# AutoDoor_App.net
KiCad netlist of a schematic drawn in Altium Designer
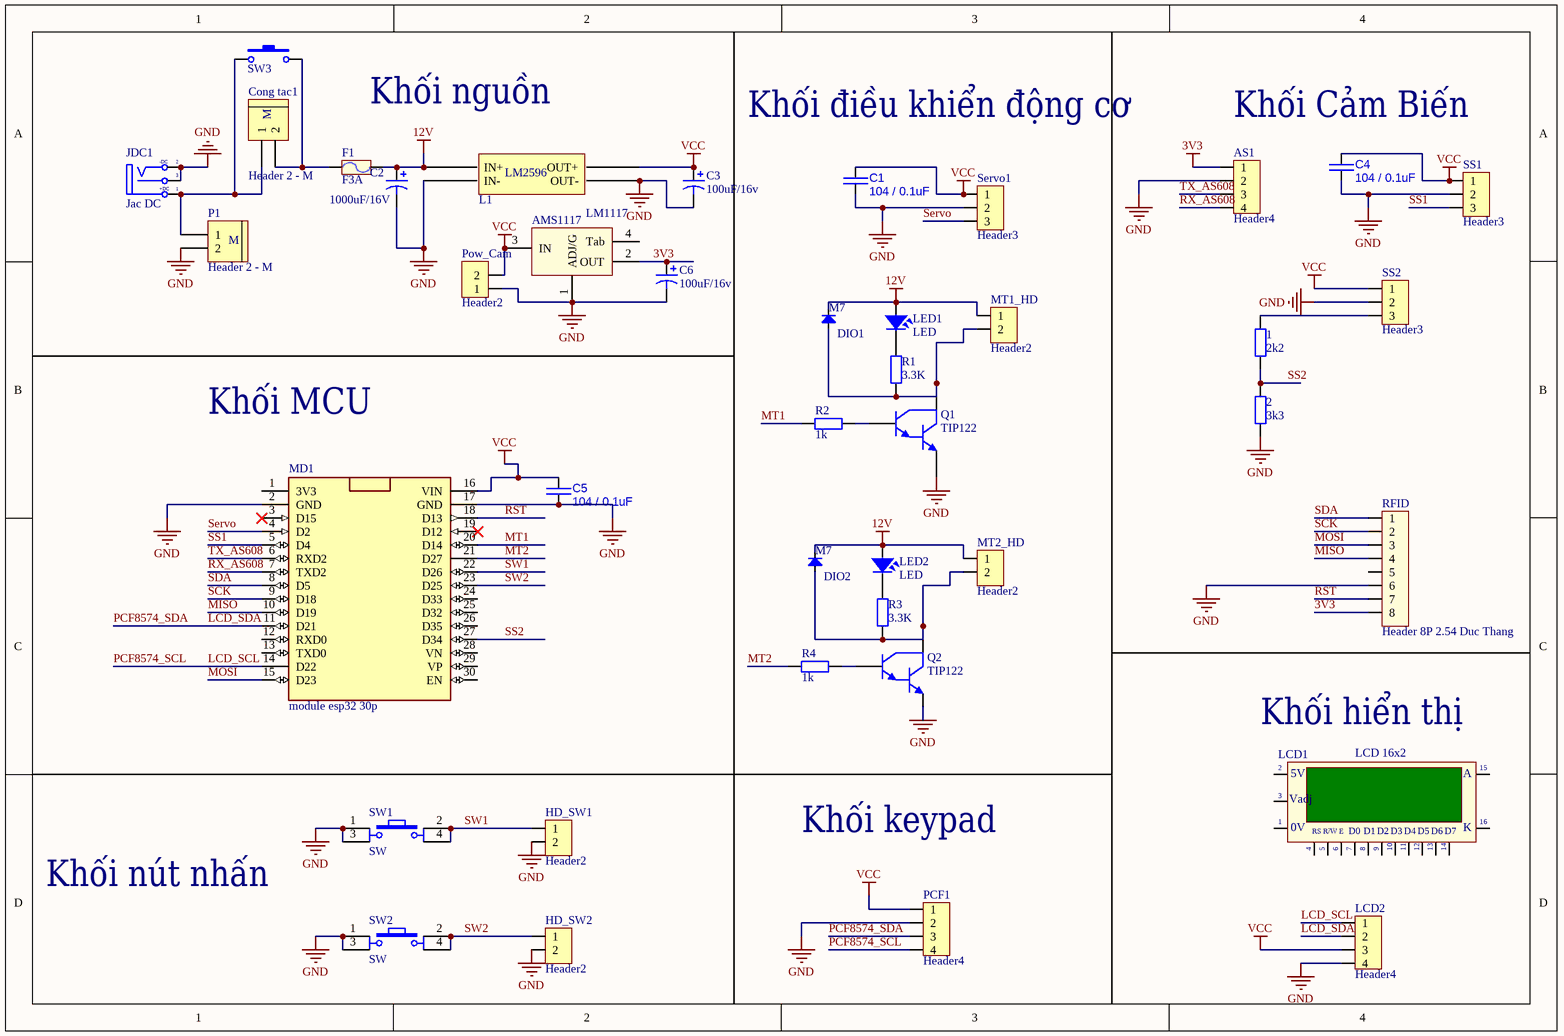
[diagram p0: AutoDoor_App.SchDoc]

(export (version "E")
  (design (tool "Eeschema 10.0.6"))
  (components
    (comp (ref "1")
      (value "2k2")
      (footprint "DIEN TRO 0805")
      (description "Resistor SMD 0805")
      (fields (field (name "PUBLISHER") "Altium Limited"))
      (libsource (lib "My Library (1)") (part "R0805"))
    )
    (comp (ref "2")
      (value "3k3")
      (footprint "DIEN TRO 0805")
      (description "Resistor SMD 0805")
      (fields (field (name "PUBLISHER") "Altium Limited"))
      (libsource (lib "My Library (1)") (part "R0805"))
    )
    (comp (ref "AMS1117")
      (value "LM1117")
      (footprint "SOT223-4N")
      (description "3v3")
      (libsource (lib "My Library") (part "LM1117"))
    )
    (comp (ref "AS1")
      (value "Header4")
      (footprint "Header4")
      (description "Header IDC, 4 x 1 Pin Vertical 2.54mm Pitch (Non-Boxed, Male)")
      (fields
        (field (name "MANUFACTURER") "Würth Elektronik eiSos GmbH")
        (field (name "PARTNO") "613002143121")
        (field (name "CREATED BY") "Karrer Zheng")
      )
      (libsource (lib "My Library") (part "Header4"))
    )
    (comp (ref "C1")
      (value "104 / 0.1uF")
      (footprint "CAP_0805")
      (description "Capacitor SMD Cer 1.8nF 10% 50V X7R 0805")
      (fields (field (name "TOLERANCE") "±10%") (field (name "Comment") "approved sub OK"))
      (libsource (lib "My library altium") (part "CAP C_0805"))
    )
    (comp (ref "C2")
      (value "1000uF/16V")
      (footprint "C10mm")
      (description "Polarized Capacitor (Axial)")
      (fields (field (name "PUBLISHER") "Altium Limited"))
      (libsource (lib "My Library") (part "Cap Pol 12mm"))
    )
    (comp (ref "C3")
      (value "100uF/16v")
      (footprint "C5mm")
      (description "Polarized Capacitor (Axial)")
      (fields (field (name "PUBLISHER") "Altium Limited"))
      (libsource (lib "My Library") (part "Cap Pol 5mm"))
    )
    (comp (ref "C4")
      (value "104 / 0.1uF")
      (footprint "CAP_0805")
      (description "Capacitor SMD Cer 1.8nF 10% 50V X7R 0805")
      (fields (field (name "TOLERANCE") "±10%") (field (name "Comment") "approved sub OK"))
      (libsource (lib "My library altium") (part "CAP C_0805"))
    )
    (comp (ref "C5")
      (value "104 / 0.1uF")
      (footprint "CAP_0805")
      (description "Capacitor SMD Cer 1.8nF 10% 50V X7R 0805")
      (fields (field (name "TOLERANCE") "±10%") (field (name "Comment") "approved sub OK"))
      (libsource (lib "My library altium") (part "CAP C_0805"))
    )
    (comp (ref "C6")
      (value "100uF/16v")
      (footprint "C5mm")
      (description "Polarized Capacitor (Axial)")
      (fields (field (name "PUBLISHER") "Altium Limited"))
      (libsource (lib "My Library") (part "Cap Pol 5mm"))
    )
    (comp (ref "Cong tac1")
      (value "Header 2 - M")
      (footprint "Medium - Header 2")
      (description "Header, 2-Pin, Medium")
      (fields (field (name "PUBLISHER") "Altium Limited"))
      (libsource (lib "My Library") (part "Header 2 - M"))
    )
    (comp (ref "DIO1")
      (value "M7")
      (footprint "DIO-SMD-106")
      (description "Default Diode")
      (fields (field (name "PUBLISHER") "Altium Limited"))
      (libsource (lib "My Library (1)") (part "Diode SMD"))
    )
    (comp (ref "DIO2")
      (value "M7")
      (footprint "DIO-SMD-106")
      (description "Default Diode")
      (fields (field (name "PUBLISHER") "Altium Limited"))
      (libsource (lib "My Library (1)") (part "Diode SMD"))
    )
    (comp (ref "F1")
      (value "F3A")
      (footprint "Fuse")
      (description "Fuse")
      (fields (field (name "DESIGNED BY") "VanDungEvn"))
      (libsource (lib "My Library") (part "Fuse"))
    )
    (comp (ref "HD_SW1")
      (value "Header2")
      (footprint "Header2")
      (description "Header IDC, 2 x 1 Pin Vertical 2.54mm Pitch (Non-Boxed, Male)")
      (fields
        (field (name "MANUFACTURER") "Würth Elektronik eiSos GmbH")
        (field (name "PARTNO") "613002143121")
        (field (name "CREATED BY") "Karrer Zheng")
      )
      (libsource (lib "My Library") (part "Header2"))
    )
    (comp (ref "HD_SW2")
      (value "Header2")
      (footprint "Header2")
      (description "Header IDC, 2 x 1 Pin Vertical 2.54mm Pitch (Non-Boxed, Male)")
      (fields
        (field (name "MANUFACTURER") "Würth Elektronik eiSos GmbH")
        (field (name "PARTNO") "613002143121")
        (field (name "CREATED BY") "Karrer Zheng")
      )
      (libsource (lib "My Library") (part "Header2"))
    )
    (comp (ref "JDC1")
      (value "Jac DC")
      (footprint "DC-IN")
      (description "Jac DC input")
      (libsource (lib "My Library") (part "DCIN"))
    )
    (comp (ref "L1")
      (value "BUCK_LM2596")
      (footprint "BUCK_LM2596")
      (libsource (lib "BUCK_LM2596_Sch") (part "BUCK_LM2596"))
    )
    (comp (ref "LCD1")
      (value "LCD 16x2")
      (footprint "LCD16X2N")
      (libsource (lib "My library altium") (part "LCD"))
    )
    (comp (ref "LCD2")
      (value "Header4")
      (footprint "XH2.54M-4")
      (description "Header IDC, 4 x 1 Pin Vertical 2.54mm Pitch (Non-Boxed, Male)")
      (fields
        (field (name "MANUFACTURER") "Würth Elektronik eiSos GmbH")
        (field (name "PARTNO") "613002143121")
        (field (name "CREATED BY") "Karrer Zheng")
      )
      (libsource (lib "My Library") (part "Header4"))
    )
    (comp (ref "LED1")
      (value "LED")
      (footprint "LED-5 GRe")
      (description "LED Single colour Green and Red")
      (libsource (lib "My Library") (part "LED"))
    )
    (comp (ref "LED2")
      (value "LED")
      (footprint "LED-5 GRe")
      (description "LED Single colour Green and Red")
      (libsource (lib "My Library") (part "LED"))
    )
    (comp (ref "MD1")
      (value "module esp32 30p")
      (footprint "module esp32 30 pin")
      (libsource (lib "Chuong Engineer") (part "module esp32 30p"))
    )
    (comp (ref "MT1_HD")
      (value "Header2")
      (footprint "Header2")
      (description "Header IDC, 2 x 1 Pin Vertical 2.54mm Pitch (Non-Boxed, Male)")
      (fields
        (field (name "MANUFACTURER") "Würth Elektronik eiSos GmbH")
        (field (name "PARTNO") "613002143121")
        (field (name "CREATED BY") "Karrer Zheng")
      )
      (libsource (lib "My Library") (part "Header2"))
    )
    (comp (ref "MT2_HD")
      (value "Header2")
      (footprint "Header2")
      (description "Header IDC, 2 x 1 Pin Vertical 2.54mm Pitch (Non-Boxed, Male)")
      (fields
        (field (name "MANUFACTURER") "Würth Elektronik eiSos GmbH")
        (field (name "PARTNO") "613002143121")
        (field (name "CREATED BY") "Karrer Zheng")
      )
      (libsource (lib "My Library") (part "Header2"))
    )
    (comp (ref "P1")
      (value "Header 2 - M")
      (footprint "Medium - Header 2")
      (description "Header, 2-Pin, Medium")
      (fields (field (name "PUBLISHER") "Altium Limited"))
      (libsource (lib "") (part "Header 2 - M_1"))
    )
    (comp (ref "PCF1")
      (value "Header4")
      (footprint "XH2.54M-4")
      (description "Header IDC, 4 x 1 Pin Vertical 2.54mm Pitch (Non-Boxed, Male)")
      (fields
        (field (name "MANUFACTURER") "Würth Elektronik eiSos GmbH")
        (field (name "PARTNO") "613002143121")
        (field (name "CREATED BY") "Karrer Zheng")
      )
      (libsource (lib "My Library") (part "Header4"))
    )
    (comp (ref "Pow_Cam")
      (value "Header2")
      (footprint "Header2")
      (description "Header IDC, 2 x 1 Pin Vertical 2.54mm Pitch (Non-Boxed, Male)")
      (fields
        (field (name "MANUFACTURER") "Würth Elektronik eiSos GmbH")
        (field (name "PARTNO") "613002143121")
        (field (name "CREATED BY") "Karrer Zheng")
      )
      (libsource (lib "") (part "Header2_1"))
    )
    (comp (ref "Q1")
      (value "TIP122")
      (footprint "QTO-220")
      (description "Darlington Silicon Power NPN Transistor, 8 Amp, 100 Volts and 65 Watts")
      (libsource (lib "My Library (1)") (part "TIP122"))
    )
    (comp (ref "Q2")
      (value "TIP122")
      (footprint "QTO-220")
      (description "Darlington Silicon Power NPN Transistor, 8 Amp, 100 Volts and 65 Watts")
      (libsource (lib "My Library (1)") (part "TIP122"))
    )
    (comp (ref "R1")
      (value "3.3K")
      (footprint "DIEN TRO 0805")
      (description "Resistor SMD 0805")
      (fields (field (name "PUBLISHER") "Altium Limited"))
      (libsource (lib "My Library (1)") (part "R0805"))
    )
    (comp (ref "R2")
      (value "1k")
      (footprint "DIEN TRO 0805")
      (description "Resistor SMD 0805")
      (fields (field (name "PUBLISHER") "Altium Limited"))
      (libsource (lib "") (part "R0805_1"))
    )
    (comp (ref "R3")
      (value "3.3K")
      (footprint "DIEN TRO 0805")
      (description "Resistor SMD 0805")
      (fields (field (name "PUBLISHER") "Altium Limited"))
      (libsource (lib "My Library (1)") (part "R0805"))
    )
    (comp (ref "R4")
      (value "1k")
      (footprint "DIEN TRO 0805")
      (description "Resistor SMD 0805")
      (fields (field (name "PUBLISHER") "Altium Limited"))
      (libsource (lib "") (part "R0805_1"))
    )
    (comp (ref "RFID")
      (value "Header 8P 2.54 Duc Thang")
      (footprint "XH2.54M-8")
      (description "Cắm")
      (libsource (lib "Header") (part "Header 8P 2.54 Duc Thang"))
    )
    (comp (ref "Servo1")
      (value "Header3")
      (footprint "Header3")
      (description "Header IDC, 3 x 1 Pin Vertical 2.54mm Pitch (Non-Boxed, Male)")
      (fields
        (field (name "MANUFACTURER") "Würth Elektronik eiSos GmbH")
        (field (name "PARTNO") "613002143121")
        (field (name "CREATED BY") "Karrer Zheng")
      )
      (libsource (lib "My Library") (part "Header3"))
    )
    (comp (ref "SS1")
      (value "Header3")
      (footprint "Header3")
      (description "Header IDC, 3 x 1 Pin Vertical 2.54mm Pitch (Non-Boxed, Male)")
      (fields
        (field (name "MANUFACTURER") "Würth Elektronik eiSos GmbH")
        (field (name "PARTNO") "613002143121")
        (field (name "CREATED BY") "Karrer Zheng")
      )
      (libsource (lib "My Library") (part "Header3"))
    )
    (comp (ref "SS2")
      (value "Header3")
      (footprint "Header3")
      (description "Header IDC, 3 x 1 Pin Vertical 2.54mm Pitch (Non-Boxed, Male)")
      (fields
        (field (name "MANUFACTURER") "Würth Elektronik eiSos GmbH")
        (field (name "PARTNO") "613002143121")
        (field (name "CREATED BY") "Karrer Zheng")
      )
      (libsource (lib "My Library") (part "Header3"))
    )
    (comp (ref "SW1")
      (value "SW")
      (footprint "SW4")
      (description "Switch button 4 pin")
      (libsource (lib "My Library (1)") (part "SW4"))
    )
    (comp (ref "SW2")
      (value "SW")
      (footprint "SW4")
      (description "Switch button 4 pin")
      (libsource (lib "My Library (1)") (part "SW4"))
    )
    (comp (ref "SW3")
      (value "KCD01-11_SWITCH")
      (footprint "KCD01-11")
      (description "Nut Nhan 2 Chan SMD 3x6x2.5")
      (libsource (lib "KS Chuong") (part "KCD01-11_SWITCH"))
    )
  )
  (nets
    (net (code "1") (name "/LCD_SCL") (class "Default")
      (node (ref "LCD2") (pin "1") (pinfunction "1_1") (pintype "passive"))
      (node (ref "MD1") (pin "14") (pinfunction "D22_14") (pintype "power_in"))
      (node (ref "PCF1") (pin "4") (pinfunction "4_4") (pintype "passive"))
    )
    (net (code "2") (name "/LCD_SDA") (class "Default")
      (node (ref "LCD2") (pin "2") (pinfunction "2_2") (pintype "passive"))
      (node (ref "MD1") (pin "11") (pinfunction "D21_11") (pintype "bidirectional"))
      (node (ref "PCF1") (pin "3") (pinfunction "3_3") (pintype "passive"))
    )
    (net (code "3") (name "/MISO") (class "Default")
      (node (ref "MD1") (pin "10") (pinfunction "D19_10") (pintype "bidirectional"))
      (node (ref "RFID") (pin "4") (pinfunction "4_4") (pintype "passive"))
    )
    (net (code "4") (name "/MOSI") (class "Default")
      (node (ref "MD1") (pin "15") (pinfunction "D23_15") (pintype "bidirectional"))
      (node (ref "RFID") (pin "3") (pinfunction "3_3") (pintype "passive"))
    )
    (net (code "5") (name "/MT1") (class "Default")
      (node (ref "MD1") (pin "20") (pinfunction "D14_20") (pintype "bidirectional"))
      (node (ref "R2") (pin "2") (pinfunction "2_2") (pintype "passive"))
    )
    (net (code "6") (name "/MT2") (class "Default")
      (node (ref "MD1") (pin "21") (pinfunction "D27_21") (pintype "power_in"))
      (node (ref "R4") (pin "2") (pinfunction "2_2") (pintype "passive"))
    )
    (net (code "7") (name "/RST") (class "Default")
      (node (ref "MD1") (pin "18") (pinfunction "D13_18") (pintype "output"))
      (node (ref "RFID") (pin "7") (pinfunction "7_7") (pintype "passive"))
    )
    (net (code "8") (name "/RX_AS608") (class "Default")
      (node (ref "AS1") (pin "4") (pinfunction "4_4") (pintype "passive"))
      (node (ref "MD1") (pin "7") (pinfunction "TXD2_7") (pintype "bidirectional"))
    )
    (net (code "9") (name "/SCK") (class "Default")
      (node (ref "MD1") (pin "9") (pinfunction "D18_9") (pintype "bidirectional"))
      (node (ref "RFID") (pin "2") (pinfunction "2_2") (pintype "passive"))
    )
    (net (code "10") (name "/SDA") (class "Default")
      (node (ref "MD1") (pin "8") (pinfunction "D5_8") (pintype "bidirectional"))
      (node (ref "RFID") (pin "1") (pinfunction "1_1") (pintype "passive"))
    )
    (net (code "11") (name "/SS1") (class "Default")
      (node (ref "MD1") (pin "5") (pinfunction "D4_5") (pintype "bidirectional"))
      (node (ref "SS1") (pin "3") (pinfunction "3_3") (pintype "passive"))
    )
    (net (code "12") (name "/SS2") (class "Default")
      (node (ref "1") (pin "2") (pinfunction "2_2") (pintype "passive"))
      (node (ref "2") (pin "1") (pinfunction "1_1") (pintype "passive"))
      (node (ref "MD1") (pin "27") (pinfunction "D34_27") (pintype "bidirectional"))
    )
    (net (code "13") (name "/SW1") (class "Default")
      (node (ref "HD_SW1") (pin "1") (pinfunction "1_1") (pintype "passive"))
      (node (ref "MD1") (pin "22") (pinfunction "D26_22") (pintype "bidirectional"))
      (node (ref "SW1") (pin "2") (pintype "passive"))
      (node (ref "SW1") (pin "4") (pintype "passive"))
    )
    (net (code "14") (name "/SW2") (class "Default")
      (node (ref "HD_SW2") (pin "1") (pinfunction "1_1") (pintype "passive"))
      (node (ref "MD1") (pin "23") (pinfunction "D25_23") (pintype "bidirectional"))
      (node (ref "SW2") (pin "2") (pintype "passive"))
      (node (ref "SW2") (pin "4") (pintype "passive"))
    )
    (net (code "15") (name "/Servo") (class "Default")
      (node (ref "MD1") (pin "4") (pinfunction "D2_4") (pintype "input"))
      (node (ref "Servo1") (pin "3") (pinfunction "3_3") (pintype "passive"))
    )
    (net (code "16") (name "/TX_AS608") (class "Default")
      (node (ref "AS1") (pin "3") (pinfunction "3_3") (pintype "passive"))
      (node (ref "MD1") (pin "6") (pinfunction "RXD2_6") (pintype "bidirectional"))
    )
    (net (code "17") (name "3V3") (class "Default")
      (node (ref "AMS1117") (pin "2") (pinfunction "OUT_2") (pintype "passive"))
      (node (ref "AS1") (pin "1") (pinfunction "1_1") (pintype "passive"))
      (node (ref "C6") (pin "1") (pinfunction "1_1") (pintype "passive"))
      (node (ref "RFID") (pin "8") (pinfunction "8_8") (pintype "passive"))
    )
    (net (code "18") (name "12V") (class "Default")
      (node (ref "C2") (pin "1") (pinfunction "1_1") (pintype "passive"))
      (node (ref "DIO1") (pin "2") (pinfunction "K_2") (pintype "passive"))
      (node (ref "DIO2") (pin "2") (pinfunction "K_2") (pintype "passive"))
      (node (ref "F1") (pin "2") (pinfunction "2_2") (pintype "passive"))
      (node (ref "L1") (pin "1") (pinfunction "IN+_1") (pintype "passive"))
      (node (ref "LED1") (pin "1") (pinfunction "1_1") (pintype "passive"))
      (node (ref "LED2") (pin "1") (pinfunction "1_1") (pintype "passive"))
      (node (ref "MT1_HD") (pin "1") (pinfunction "1_1") (pintype "passive"))
      (node (ref "MT2_HD") (pin "1") (pinfunction "1_1") (pintype "passive"))
    )
    (net (code "19") (name "GND") (class "Default")
      (node (ref "2") (pin "2") (pinfunction "2_2") (pintype "passive"))
      (node (ref "AMS1117") (pin "1") (pinfunction "ADJ/G_1") (pintype "passive"))
      (node (ref "AS1") (pin "2") (pinfunction "2_2") (pintype "passive"))
      (node (ref "C1") (pin "1") (pintype "passive"))
      (node (ref "C2") (pin "2") (pinfunction "2_2") (pintype "passive"))
      (node (ref "C3") (pin "2") (pinfunction "2_2") (pintype "passive"))
      (node (ref "C4") (pin "1") (pintype "passive"))
      (node (ref "C5") (pin "1") (pintype "passive"))
      (node (ref "C6") (pin "2") (pinfunction "2_2") (pintype "passive"))
      (node (ref "HD_SW1") (pin "2") (pinfunction "2_2") (pintype "passive"))
      (node (ref "HD_SW2") (pin "2") (pinfunction "2_2") (pintype "passive"))
      (node (ref "JDC1") (pin "2") (pinfunction "TN_2") (pintype "passive"))
      (node (ref "JDC1") (pin "3") (pinfunction "S_3") (pintype "power_in"))
      (node (ref "L1") (pin "2") (pinfunction "IN-_2") (pintype "passive"))
      (node (ref "L1") (pin "3") (pinfunction "OUT-_3") (pintype "passive"))
      (node (ref "LCD2") (pin "4") (pinfunction "4_4") (pintype "passive"))
      (node (ref "MD1") (pin "17") (pinfunction "GND_17") (pintype "power_in"))
      (node (ref "MD1") (pin "2") (pinfunction "GND_2") (pintype "power_in"))
      (node (ref "P1") (pin "2") (pinfunction "2_2") (pintype "passive"))
      (node (ref "PCF1") (pin "2") (pinfunction "2_2") (pintype "passive"))
      (node (ref "Pow_Cam") (pin "1") (pinfunction "1_1") (pintype "passive"))
      (node (ref "Q1") (pin "3") (pinfunction "E_3") (pintype "passive"))
      (node (ref "Q2") (pin "3") (pinfunction "E_3") (pintype "passive"))
      (node (ref "RFID") (pin "6") (pinfunction "6_6") (pintype "passive"))
      (node (ref "SS1") (pin "2") (pinfunction "2_2") (pintype "passive"))
      (node (ref "SS2") (pin "2") (pinfunction "2_2") (pintype "passive"))
      (node (ref "SW1") (pin "1") (pintype "passive"))
      (node (ref "SW1") (pin "3") (pintype "passive"))
      (node (ref "SW2") (pin "1") (pintype "passive"))
      (node (ref "SW2") (pin "3") (pintype "passive"))
      (node (ref "Servo1") (pin "2") (pinfunction "2_2") (pintype "passive"))
    )
    (net (code "20") (name "Net-(1-Pad1)") (class "Default")
      (node (ref "1") (pin "1") (pinfunction "1_1") (pintype "passive"))
      (node (ref "SS2") (pin "3") (pinfunction "3_3") (pintype "passive"))
    )
    (net (code "21") (name "Net-(Cong tac1-Pad2)") (class "Default")
      (node (ref "Cong tac1") (pin "2") (pinfunction "2_2") (pintype "passive"))
      (node (ref "F1") (pin "1") (pinfunction "1_1") (pintype "passive"))
      (node (ref "SW3") (pin "2") (pinfunction "2_2") (pintype "passive"))
    )
    (net (code "22") (name "Net-(DIO1-A)") (class "Default")
      (node (ref "DIO1") (pin "1") (pinfunction "A_1") (pintype "passive"))
      (node (ref "MT1_HD") (pin "2") (pinfunction "2_2") (pintype "passive"))
      (node (ref "Q1") (pin "2") (pinfunction "C_2") (pintype "passive"))
      (node (ref "R1") (pin "2") (pinfunction "2_2") (pintype "passive"))
    )
    (net (code "23") (name "Net-(DIO2-A)") (class "Default")
      (node (ref "DIO2") (pin "1") (pinfunction "A_1") (pintype "passive"))
      (node (ref "MT2_HD") (pin "2") (pinfunction "2_2") (pintype "passive"))
      (node (ref "Q2") (pin "2") (pinfunction "C_2") (pintype "passive"))
      (node (ref "R3") (pin "2") (pinfunction "2_2") (pintype "passive"))
    )
    (net (code "24") (name "Net-(JDC1-T)") (class "Default")
      (node (ref "Cong tac1") (pin "1") (pinfunction "1_1") (pintype "passive"))
      (node (ref "JDC1") (pin "1") (pinfunction "T_1") (pintype "passive"))
      (node (ref "P1") (pin "1") (pinfunction "1_1") (pintype "passive"))
      (node (ref "SW3") (pin "1") (pinfunction "1_1") (pintype "passive"))
    )
    (net (code "25") (name "Net-(LED1-Pad2)") (class "Default")
      (node (ref "LED1") (pin "2") (pinfunction "2_2") (pintype "passive"))
      (node (ref "R1") (pin "1") (pinfunction "1_1") (pintype "passive"))
    )
    (net (code "26") (name "Net-(LED2-Pad2)") (class "Default")
      (node (ref "LED2") (pin "2") (pinfunction "2_2") (pintype "passive"))
      (node (ref "R3") (pin "1") (pinfunction "1_1") (pintype "passive"))
    )
    (net (code "27") (name "Net-(Q1-B)") (class "Default")
      (node (ref "Q1") (pin "1") (pinfunction "B_1") (pintype "passive"))
      (node (ref "R2") (pin "1") (pinfunction "1_1") (pintype "passive"))
    )
    (net (code "28") (name "Net-(Q2-B)") (class "Default")
      (node (ref "Q2") (pin "1") (pinfunction "B_1") (pintype "passive"))
      (node (ref "R4") (pin "1") (pinfunction "1_1") (pintype "passive"))
    )
    (net (code "29") (name "VCC") (class "Default")
      (node (ref "AMS1117") (pin "3") (pinfunction "IN_3") (pintype "passive"))
      (node (ref "C1") (pin "2") (pintype "passive"))
      (node (ref "C3") (pin "1") (pinfunction "1_1") (pintype "passive"))
      (node (ref "C4") (pin "2") (pintype "passive"))
      (node (ref "C5") (pin "2") (pintype "passive"))
      (node (ref "L1") (pin "4") (pinfunction "OUT+_4") (pintype "passive"))
      (node (ref "LCD2") (pin "3") (pinfunction "3_3") (pintype "passive"))
      (node (ref "MD1") (pin "16") (pinfunction "VIN_16") (pintype "power_in"))
      (node (ref "PCF1") (pin "1") (pinfunction "1_1") (pintype "passive"))
      (node (ref "Pow_Cam") (pin "2") (pinfunction "2_2") (pintype "passive"))
      (node (ref "SS1") (pin "1") (pinfunction "1_1") (pintype "passive"))
      (node (ref "SS2") (pin "1") (pinfunction "1_1") (pintype "passive"))
      (node (ref "Servo1") (pin "1") (pinfunction "1_1") (pintype "passive"))
    )
    (net (code "30") (name "unconnected-(AMS1117-Tab-Pad4)") (class "Default")
      (node (ref "AMS1117") (pin "4") (pinfunction "Tab_4") (pintype "passive"))
    )
    (net (code "31") (name "unconnected-(LCD1-A-Pad15)") (class "Default")
      (node (ref "LCD1") (pin "15") (pinfunction "A_15") (pintype "passive"))
    )
    (net (code "32") (name "unconnected-(LCD1-D0-Pad7)") (class "Default")
      (node (ref "LCD1") (pin "7") (pinfunction "D0_7") (pintype "passive"))
    )
    (net (code "33") (name "unconnected-(LCD1-D1-Pad8)") (class "Default")
      (node (ref "LCD1") (pin "8") (pinfunction "D1_8") (pintype "passive"))
    )
    (net (code "34") (name "unconnected-(LCD1-D2-Pad9)") (class "Default")
      (node (ref "LCD1") (pin "9") (pinfunction "D2_9") (pintype "passive"))
    )
    (net (code "35") (name "unconnected-(LCD1-D3-Pad10)") (class "Default")
      (node (ref "LCD1") (pin "10") (pinfunction "D3_10") (pintype "passive"))
    )
    (net (code "36") (name "unconnected-(LCD1-D4-Pad11)") (class "Default")
      (node (ref "LCD1") (pin "11") (pinfunction "D4_11") (pintype "passive"))
    )
    (net (code "37") (name "unconnected-(LCD1-D5-Pad12)") (class "Default")
      (node (ref "LCD1") (pin "12") (pinfunction "D5_12") (pintype "passive"))
    )
    (net (code "38") (name "unconnected-(LCD1-D6-Pad13)") (class "Default")
      (node (ref "LCD1") (pin "13") (pinfunction "D6_13") (pintype "passive"))
    )
    (net (code "39") (name "unconnected-(LCD1-D7-Pad14)") (class "Default")
      (node (ref "LCD1") (pin "14") (pinfunction "D7_14") (pintype "passive"))
    )
    (net (code "40") (name "unconnected-(LCD1-GND-Pad1)") (class "Default")
      (node (ref "LCD1") (pin "1") (pinfunction "GND_1") (pintype "passive"))
    )
    (net (code "41") (name "unconnected-(LCD1-K-Pad16)") (class "Default")
      (node (ref "LCD1") (pin "16") (pinfunction "K_16") (pintype "passive"))
    )
    (net (code "42") (name "unconnected-(LCD1-RS-Pad4)") (class "Default")
      (node (ref "LCD1") (pin "4") (pinfunction "RS_4") (pintype "passive"))
    )
    (net (code "43") (name "unconnected-(LCD1-R{slash}~{W}-Pad5)") (class "Default")
      (node (ref "LCD1") (pin "5") (pinfunction "R/~{W}_5") (pintype "passive"))
    )
    (net (code "44") (name "unconnected-(LCD1-VAdj-Pad3)") (class "Default")
      (node (ref "LCD1") (pin "3") (pinfunction "VAdj_3") (pintype "passive"))
    )
    (net (code "45") (name "unconnected-(LCD1-VDD-Pad2)") (class "Default")
      (node (ref "LCD1") (pin "2") (pinfunction "VDD_2") (pintype "passive"))
    )
    (net (code "46") (name "unconnected-(LCD1-~{EN}-Pad6)") (class "Default")
      (node (ref "LCD1") (pin "6") (pinfunction "~{EN}_6") (pintype "passive"))
    )
    (net (code "47") (name "unconnected-(MD1-3V3-Pad1)") (class "Default")
      (node (ref "MD1") (pin "1") (pinfunction "3V3_1") (pintype "power_in"))
    )
    (net (code "48") (name "unconnected-(MD1-D12-Pad19)") (class "Default")
      (node (ref "MD1") (pin "19") (pinfunction "D12_19") (pintype "input+no_connect"))
    )
    (net (code "49") (name "unconnected-(MD1-D15-Pad3)") (class "Default")
      (node (ref "MD1") (pin "3") (pinfunction "D15_3") (pintype "input+no_connect"))
    )
    (net (code "50") (name "unconnected-(MD1-D32-Pad25)") (class "Default")
      (node (ref "MD1") (pin "25") (pinfunction "D32_25") (pintype "bidirectional"))
    )
    (net (code "51") (name "unconnected-(MD1-D33-Pad24)") (class "Default")
      (node (ref "MD1") (pin "24") (pinfunction "D33_24") (pintype "bidirectional"))
    )
    (net (code "52") (name "unconnected-(MD1-D35-Pad26)") (class "Default")
      (node (ref "MD1") (pin "26") (pinfunction "D35_26") (pintype "bidirectional"))
    )
    (net (code "53") (name "unconnected-(MD1-EN-Pad30)") (class "Default")
      (node (ref "MD1") (pin "30") (pinfunction "EN_30") (pintype "bidirectional"))
    )
    (net (code "54") (name "unconnected-(MD1-RXD0-Pad12)") (class "Default")
      (node (ref "MD1") (pin "12") (pinfunction "RXD0_12") (pintype "bidirectional"))
    )
    (net (code "55") (name "unconnected-(MD1-TXD0-Pad13)") (class "Default")
      (node (ref "MD1") (pin "13") (pinfunction "TXD0_13") (pintype "bidirectional"))
    )
    (net (code "56") (name "unconnected-(MD1-VN-Pad28)") (class "Default")
      (node (ref "MD1") (pin "28") (pinfunction "VN_28") (pintype "bidirectional"))
    )
    (net (code "57") (name "unconnected-(MD1-VP-Pad29)") (class "Default")
      (node (ref "MD1") (pin "29") (pinfunction "VP_29") (pintype "bidirectional"))
    )
    (net (code "58") (name "unconnected-(RFID-Pad5)") (class "Default")
      (node (ref "RFID") (pin "5") (pinfunction "5_5") (pintype "passive"))
    )
  )
)
